# SIPO.net
KiCad netlist of a schematic drawn in Altium Designer
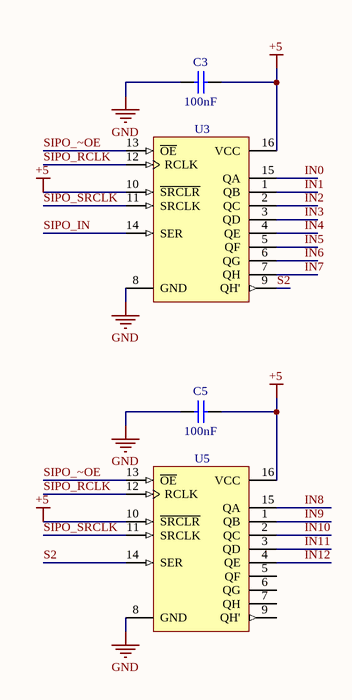
[diagram p0: SIPO.SchDoc]

(export (version "E")
  (design (tool "Eeschema 10.0.6"))
  (components
    (comp (ref "C3")
      (value "100nF")
      (footprint "C1206")
      (fields
        (field (name "Comment") "http://www.tme.eu/pl/details/12061c104kat2a/kondensatory-mlcc-smd-1206/avx/")
        (field (name "PUBLISHER") "Altium Limited")
      )
      (libsource (lib "Miscellaneous Devices") (part "Cap"))
    )
    (comp (ref "C5")
      (value "100nF")
      (footprint "C1206")
      (fields
        (field (name "Comment") "http://www.tme.eu/pl/details/12061c104kat2a/kondensatory-mlcc-smd-1206/avx/")
        (field (name "PUBLISHER") "Altium Limited")
      )
      (libsource (lib "Miscellaneous Devices") (part "Cap"))
    )
    (comp (ref "U3")
      (value "http://www.tme.eu/pl/details/sn74hc595d/rejestry-przesuwne/texas-instruments/")
      (footprint "SOIC16_N")
      (description "SN74HC595")
      (fields (field (name "PUBLISHER") "Altium Limited"))
      (libsource (lib "TI Logic Register") (part "SN74HC595N"))
    )
    (comp (ref "U5")
      (value "http://www.tme.eu/pl/details/sn74hc595d/rejestry-przesuwne/texas-instruments/")
      (footprint "SOIC16_N")
      (description "SN74HC595")
      (fields (field (name "PUBLISHER") "Altium Limited"))
      (libsource (lib "TI Logic Register") (part "SN74HC595N"))
    )
  )
  (nets
    (net (code "1") (name "+5") (class "Default")
      (node (ref "C3") (pin "2") (pinfunction "2_2") (pintype "passive"))
      (node (ref "C5") (pin "2") (pinfunction "2_2") (pintype "passive"))
      (node (ref "U3") (pin "10") (pinfunction "~{SRCLR}_10") (pintype "input"))
      (node (ref "U3") (pin "16") (pinfunction "VCC_16") (pintype "power_in"))
      (node (ref "U5") (pin "10") (pinfunction "~{SRCLR}_10") (pintype "input"))
      (node (ref "U5") (pin "16") (pinfunction "VCC_16") (pintype "power_in"))
    )
    (net (code "2") (name "/IN0") (class "Default")
      (node (ref "U3") (pin "15") (pinfunction "QA_15") (pintype "tri_state"))
    )
    (net (code "3") (name "/IN1") (class "Default")
      (node (ref "U3") (pin "1") (pinfunction "QB_1") (pintype "tri_state"))
    )
    (net (code "4") (name "/IN2") (class "Default")
      (node (ref "U3") (pin "2") (pinfunction "QC_2") (pintype "tri_state"))
    )
    (net (code "5") (name "/IN3") (class "Default")
      (node (ref "U3") (pin "3") (pinfunction "QD_3") (pintype "tri_state"))
    )
    (net (code "6") (name "/IN4") (class "Default")
      (node (ref "U3") (pin "4") (pinfunction "QE_4") (pintype "tri_state"))
    )
    (net (code "7") (name "/IN5") (class "Default")
      (node (ref "U3") (pin "5") (pinfunction "QF_5") (pintype "tri_state"))
    )
    (net (code "8") (name "/IN6") (class "Default")
      (node (ref "U3") (pin "6") (pinfunction "QG_6") (pintype "tri_state"))
    )
    (net (code "9") (name "/IN7") (class "Default")
      (node (ref "U3") (pin "7") (pinfunction "QH_7") (pintype "tri_state"))
    )
    (net (code "10") (name "/IN8") (class "Default")
      (node (ref "U5") (pin "15") (pinfunction "QA_15") (pintype "tri_state"))
    )
    (net (code "11") (name "/IN9") (class "Default")
      (node (ref "U5") (pin "1") (pinfunction "QB_1") (pintype "tri_state"))
    )
    (net (code "12") (name "/IN10") (class "Default")
      (node (ref "U5") (pin "2") (pinfunction "QC_2") (pintype "tri_state"))
    )
    (net (code "13") (name "/IN11") (class "Default")
      (node (ref "U5") (pin "3") (pinfunction "QD_3") (pintype "tri_state"))
    )
    (net (code "14") (name "/IN12") (class "Default")
      (node (ref "U5") (pin "4") (pinfunction "QE_4") (pintype "tri_state"))
    )
    (net (code "15") (name "/S2") (class "Default")
      (node (ref "U3") (pin "9") (pinfunction "QH'_9") (pintype "output"))
      (node (ref "U5") (pin "14") (pinfunction "SER_14") (pintype "input"))
    )
    (net (code "16") (name "/SIPO_IN") (class "Default")
      (node (ref "U3") (pin "14") (pinfunction "SER_14") (pintype "input"))
    )
    (net (code "17") (name "/SIPO_RCLK") (class "Default")
      (node (ref "U3") (pin "12") (pinfunction "RCLK_12") (pintype "input"))
      (node (ref "U5") (pin "12") (pinfunction "RCLK_12") (pintype "input"))
    )
    (net (code "18") (name "/SIPO_SRCLK") (class "Default")
      (node (ref "U3") (pin "11") (pinfunction "SRCLK_11") (pintype "input"))
      (node (ref "U5") (pin "11") (pinfunction "SRCLK_11") (pintype "input"))
    )
    (net (code "19") (name "/SIPO_~OE") (class "Default")
      (node (ref "U3") (pin "13") (pinfunction "~{OE}_13") (pintype "input"))
      (node (ref "U5") (pin "13") (pinfunction "~{OE}_13") (pintype "input"))
    )
    (net (code "20") (name "GND") (class "Default")
      (node (ref "C3") (pin "1") (pinfunction "1_1") (pintype "passive"))
      (node (ref "C5") (pin "1") (pinfunction "1_1") (pintype "passive"))
      (node (ref "U3") (pin "8") (pinfunction "GND_8") (pintype "power_in"))
      (node (ref "U5") (pin "8") (pinfunction "GND_8") (pintype "power_in"))
    )
    (net (code "21") (name "unconnected-(U5-QF-Pad5)") (class "Default")
      (node (ref "U5") (pin "5") (pinfunction "QF_5") (pintype "tri_state"))
    )
    (net (code "22") (name "unconnected-(U5-QG-Pad6)") (class "Default")
      (node (ref "U5") (pin "6") (pinfunction "QG_6") (pintype "tri_state"))
    )
    (net (code "23") (name "unconnected-(U5-QH'-Pad9)") (class "Default")
      (node (ref "U5") (pin "9") (pinfunction "QH'_9") (pintype "output"))
    )
    (net (code "24") (name "unconnected-(U5-QH-Pad7)") (class "Default")
      (node (ref "U5") (pin "7") (pinfunction "QH_7") (pintype "tri_state"))
    )
  )
)
